# Driver.net
KiCad netlist of a schematic drawn in Altium Designer
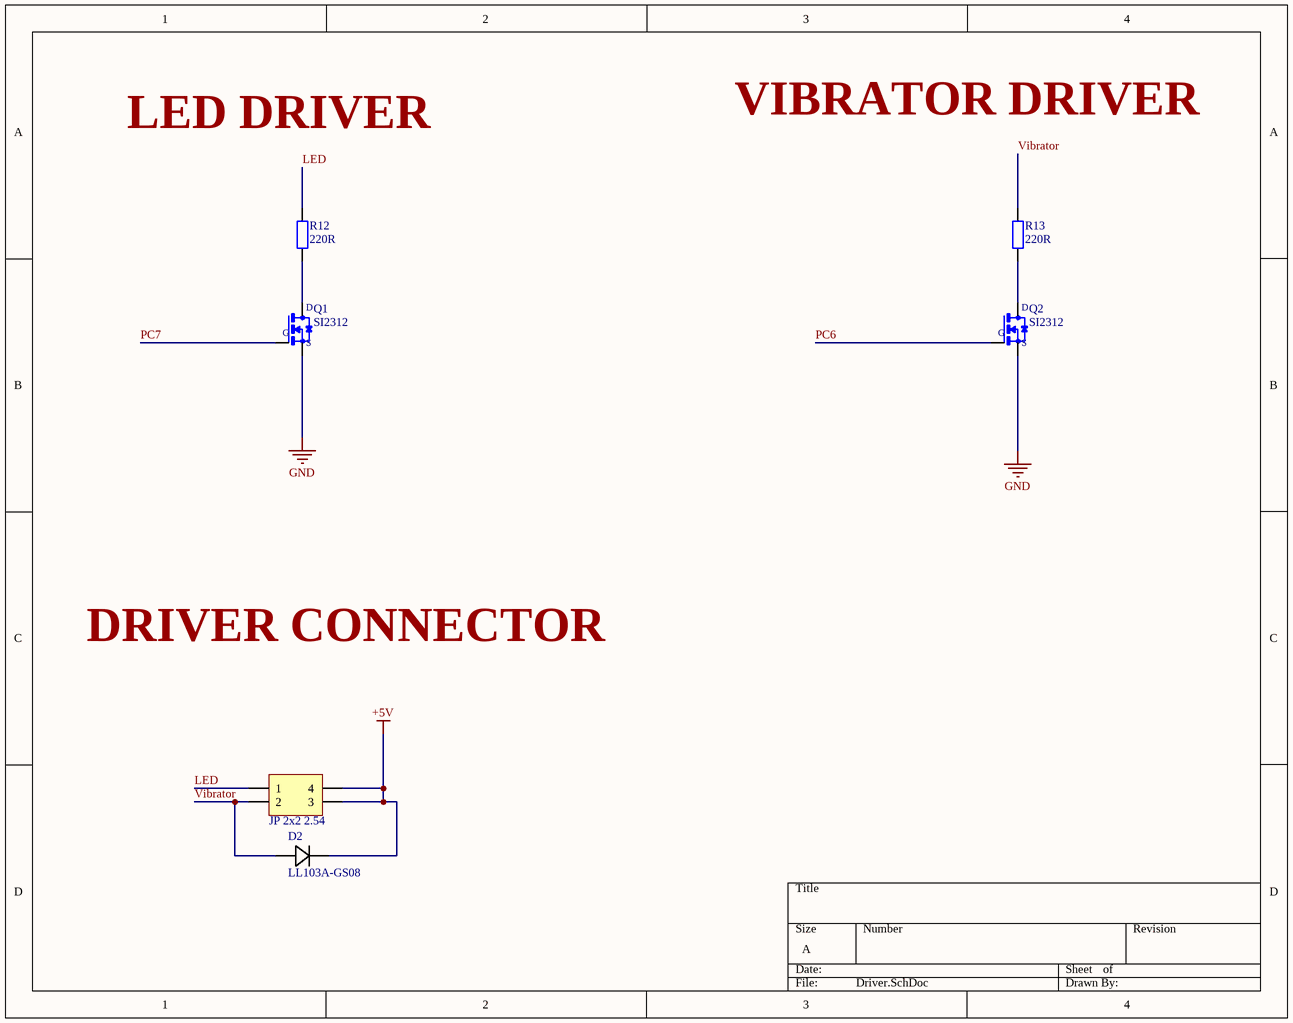
[diagram p0: Driver.SchDoc]

(export (version "E")
  (design (tool "Eeschema 10.0.6"))
  (components
    (comp (ref "D2")
      (value "LL103A-GS08")
      (footprint "MELF_SOD-80_VIS")
      (description "No Description Available")
      (libsource (lib "LL103A-GS08") (part "LL103A-GS08"))
    )
    (comp (ref "JP1")
      (value "JP 2x2 2.54")
      (footprint "JP 2x2 DT")
      (description "Cắm")
      (libsource (lib "Altium_Lib_by_KhueNguyenCreator") (part "JP 2x2 2.54 Duc Thang"))
    )
    (comp (ref "Q1")
      (value "SI2312")
      (footprint "SI2312-TP:SOT23")
      (fields
        (field (name "MF") "{'manufacturer': u'Micro Commercial Components'}")
        (field (name "MP") "SI2312-TP")
      )
      (libsource (lib "*") (part "SI2312"))
    )
    (comp (ref "Q2")
      (value "SI2312")
      (footprint "SI2312-TP:SOT23")
      (fields
        (field (name "MF") "{'manufacturer': u'Micro Commercial Components'}")
        (field (name "MP") "SI2312-TP")
      )
      (libsource (lib "*") (part "SI2312"))
    )
    (comp (ref "R12")
      (value "220R")
      (footprint "tro smd 0603")
      (description "Dán")
      (libsource (lib "Altium_Lib_by_KhueNguyenCreator") (part "Tro 0603 5% 220R"))
    )
    (comp (ref "R13")
      (value "220R")
      (footprint "tro smd 0603")
      (description "Dán")
      (libsource (lib "Altium_Lib_by_KhueNguyenCreator") (part "Tro 0603 5% 220R"))
    )
  )
  (nets
    (net (code "1") (name "+5V") (class "Default")
      (node (ref "D2") (pin "1") (pinfunction "1_1") (pintype "passive"))
      (node (ref "JP1") (pin "3") (pinfunction "3_3") (pintype "passive"))
      (node (ref "JP1") (pin "4") (pinfunction "4_4") (pintype "passive"))
    )
    (net (code "2") (name "/LED") (class "Default")
      (node (ref "JP1") (pin "1") (pinfunction "1_1") (pintype "passive"))
      (node (ref "R12") (pin "2") (pinfunction "2_2") (pintype "passive"))
    )
    (net (code "3") (name "/PC6") (class "Default")
      (node (ref "Q2") (pin "1") (pinfunction "G_1") (pintype "passive"))
    )
    (net (code "4") (name "/PC7") (class "Default")
      (node (ref "Q1") (pin "1") (pinfunction "G_1") (pintype "passive"))
    )
    (net (code "5") (name "/Vibrator") (class "Default")
      (node (ref "D2") (pin "2") (pinfunction "2_2") (pintype "passive"))
      (node (ref "JP1") (pin "2") (pinfunction "2_2") (pintype "passive"))
      (node (ref "R13") (pin "2") (pinfunction "2_2") (pintype "passive"))
    )
    (net (code "6") (name "GND") (class "Default")
      (node (ref "Q1") (pin "2") (pinfunction "S_2") (pintype "passive"))
      (node (ref "Q2") (pin "2") (pinfunction "S_2") (pintype "passive"))
    )
    (net (code "7") (name "Net-(Q1-D)") (class "Default")
      (node (ref "Q1") (pin "3") (pinfunction "D_3") (pintype "passive"))
      (node (ref "R12") (pin "1") (pinfunction "1_1") (pintype "passive"))
    )
    (net (code "8") (name "Net-(Q2-D)") (class "Default")
      (node (ref "Q2") (pin "3") (pinfunction "D_3") (pintype "passive"))
      (node (ref "R13") (pin "1") (pinfunction "1_1") (pintype "passive"))
    )
  )
)
